# pic32.net
KiCad netlist of a schematic drawn in EAGLE
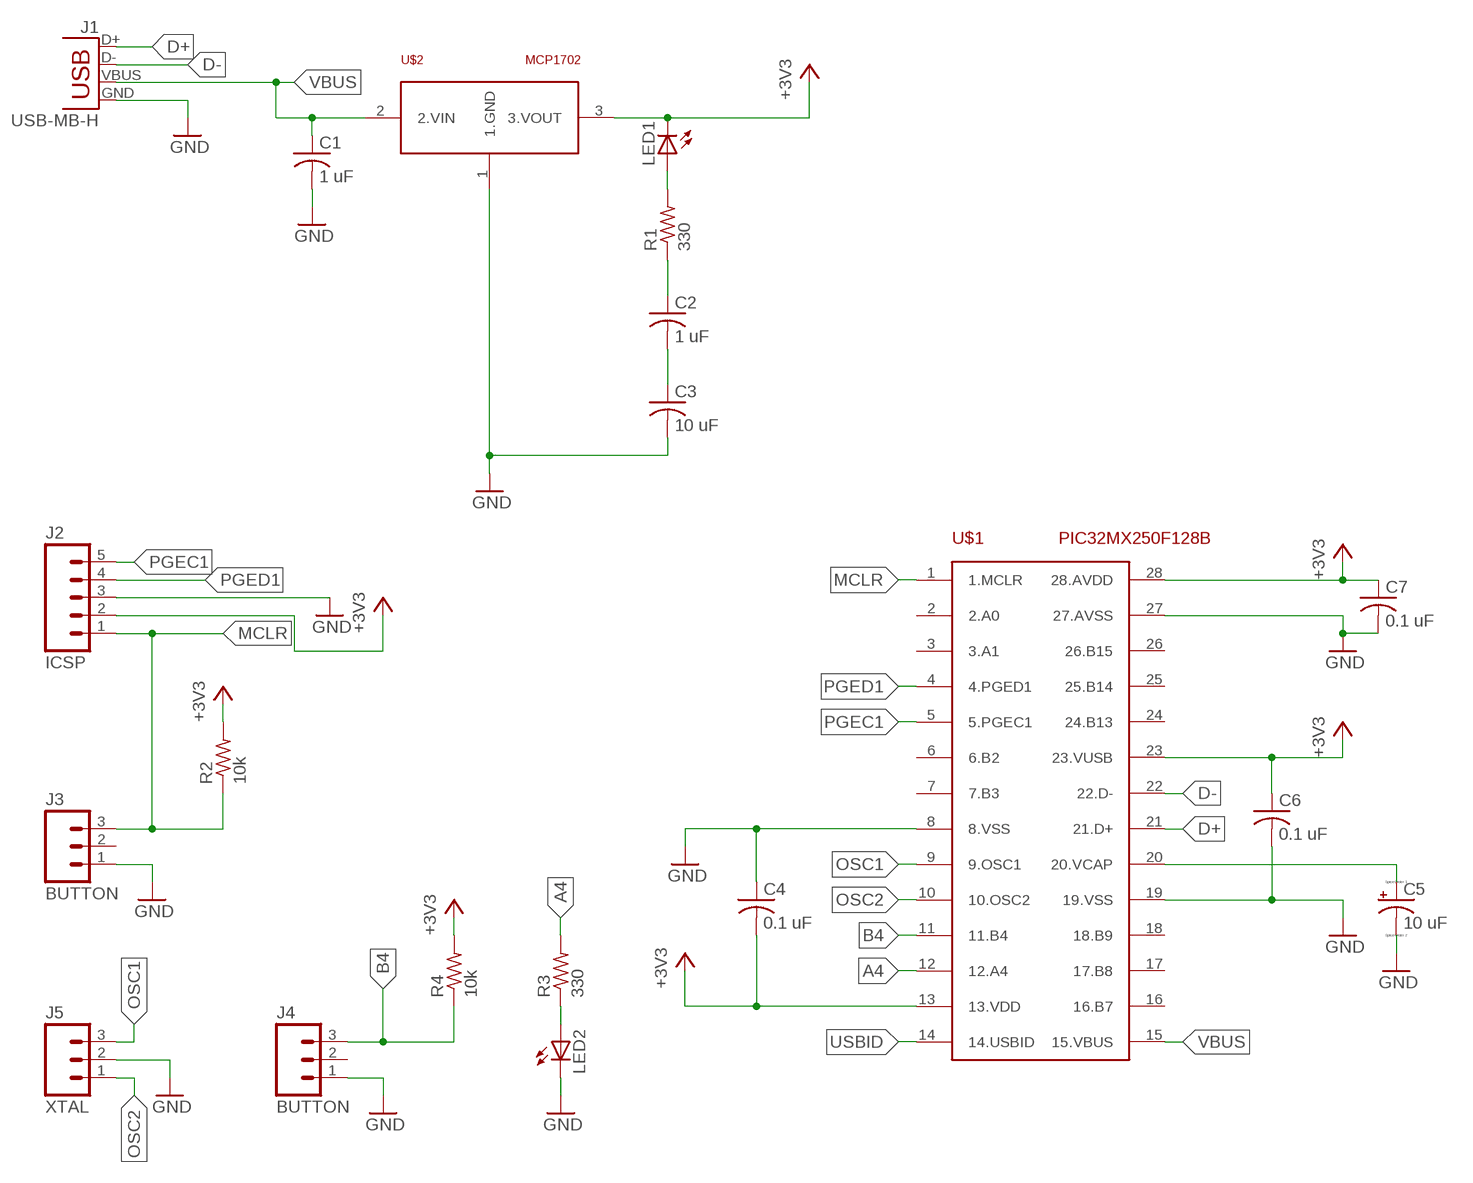
[diagram p0: schematic, sheet 1]

(export (version "E")
  (design (tool "Eeschema 10.0.6"))
  (components
    (comp (ref "C1")
      (value "1 uF")
      (footprint "eagle-import:C025-024X044")
      (libsource (lib "eagle-import") (part "C-US025-024X044"))
    )
    (comp (ref "C2")
      (value "1 uF")
      (footprint "eagle-import:C025-024X044")
      (libsource (lib "eagle-import") (part "C-US025-024X044"))
    )
    (comp (ref "C3")
      (value "10 uF")
      (footprint "eagle-import:C025-024X044")
      (libsource (lib "eagle-import") (part "C-US025-024X044"))
    )
    (comp (ref "C4")
      (value "0.1 uF")
      (footprint "eagle-import:C025-024X044")
      (libsource (lib "eagle-import") (part "C-US025-024X044"))
    )
    (comp (ref "C5")
      (value "10 uF")
      (footprint "eagle-import:E1,8-4")
      (libsource (lib "eagle-import") (part "CPOL-USE1.8-4"))
    )
    (comp (ref "C6")
      (value "0.1 uF")
      (footprint "eagle-import:C025-024X044")
      (libsource (lib "eagle-import") (part "C-US025-024X044"))
    )
    (comp (ref "C7")
      (value "0.1 uF")
      (footprint "eagle-import:C025-024X044")
      (libsource (lib "eagle-import") (part "C-US025-024X044"))
    )
    (comp (ref "J1")
      (value "USB-MB-H")
      (footprint "eagle-import:USB-MB-H")
      (libsource (lib "eagle-import") (part "USB-MB-H"))
    )
    (comp (ref "J2")
      (value "ICSP")
      (footprint "eagle-import:1X05")
      (libsource (lib "eagle-import") (part "M05PTH"))
    )
    (comp (ref "J3")
      (value "BUTTON")
      (footprint "eagle-import:1X03")
      (libsource (lib "eagle-import") (part "M03PTH"))
    )
    (comp (ref "J4")
      (value "BUTTON")
      (footprint "eagle-import:1X03")
      (libsource (lib "eagle-import") (part "M03PTH"))
    )
    (comp (ref "J5")
      (value "XTAL")
      (footprint "eagle-import:1X03")
      (libsource (lib "eagle-import") (part "M03PTH"))
    )
    (comp (ref "LED1")
      (value "LED3MM")
      (footprint "eagle-import:LED3MM")
      (libsource (lib "eagle-import") (part "LED3MM"))
    )
    (comp (ref "LED2")
      (value "LED3MM")
      (footprint "eagle-import:LED3MM")
      (libsource (lib "eagle-import") (part "LED3MM"))
    )
    (comp (ref "R1")
      (value "330")
      (footprint "eagle-import:0207_10")
      (libsource (lib "eagle-import") (part "R-US_0207/10"))
    )
    (comp (ref "R2")
      (value "10k")
      (footprint "eagle-import:0207_10")
      (libsource (lib "eagle-import") (part "R-US_0207/10"))
    )
    (comp (ref "R3")
      (value "330")
      (footprint "eagle-import:0207_10")
      (libsource (lib "eagle-import") (part "R-US_0207/10"))
    )
    (comp (ref "R4")
      (value "10k")
      (footprint "eagle-import:0207_10")
      (libsource (lib "eagle-import") (part "R-US_0207/10"))
    )
    (comp (ref "U$1")
      (value "PIC32MX250F128B")
      (footprint "eagle-import:DIL28-3")
      (libsource (lib "eagle-import") (part "PIC32MX250F128B"))
    )
    (comp (ref "U$2")
      (value "MCP1702")
      (footprint "eagle-import:TO92")
      (libsource (lib "eagle-import") (part "MCP1702"))
    )
  )
  (nets
    (net (code "1") (name "+3V3") (class "Default")
      (node (ref "C4") (pin "2") (pinfunction "2_2") (pintype "passive"))
      (node (ref "C6") (pin "1") (pinfunction "1_1") (pintype "passive"))
      (node (ref "C7") (pin "1") (pinfunction "1_1") (pintype "passive"))
      (node (ref "J2") (pin "2") (pinfunction "2_2") (pintype "passive"))
      (node (ref "LED1") (pin "K") (pinfunction "C_K") (pintype "passive"))
      (node (ref "R2") (pin "2") (pinfunction "2_2") (pintype "passive"))
      (node (ref "R4") (pin "2") (pinfunction "2_2") (pintype "passive"))
      (node (ref "U$1") (pin "13") (pinfunction "13.VDD_13") (pintype "bidirectional"))
      (node (ref "U$1") (pin "23") (pinfunction "23.VUSB_23") (pintype "bidirectional"))
      (node (ref "U$1") (pin "28") (pinfunction "28.AVDD_28") (pintype "bidirectional"))
      (node (ref "U$2") (pin "3") (pinfunction "3.VOUT_3") (pintype "bidirectional"))
    )
    (net (code "2") (name "A4") (class "Default")
      (node (ref "R3") (pin "2") (pinfunction "2_2") (pintype "passive"))
      (node (ref "U$1") (pin "12") (pinfunction "12.A4_12") (pintype "bidirectional"))
    )
    (net (code "3") (name "B4") (class "Default")
      (node (ref "J4") (pin "3") (pinfunction "3_3") (pintype "passive"))
      (node (ref "R4") (pin "1") (pinfunction "1_1") (pintype "passive"))
      (node (ref "U$1") (pin "11") (pinfunction "11.B4_11") (pintype "bidirectional"))
    )
    (net (code "4") (name "D+") (class "Default")
      (node (ref "J1") (pin "D+") (pinfunction "D+_D+") (pintype "bidirectional"))
      (node (ref "U$1") (pin "21") (pinfunction "21.D+_21") (pintype "bidirectional"))
    )
    (net (code "5") (name "D-") (class "Default")
      (node (ref "J1") (pin "D-") (pinfunction "D-_D-") (pintype "bidirectional"))
      (node (ref "U$1") (pin "22") (pinfunction "22.D-_22") (pintype "bidirectional"))
    )
    (net (code "6") (name "GND") (class "Default")
      (node (ref "C1") (pin "2") (pinfunction "2_2") (pintype "passive"))
      (node (ref "C3") (pin "2") (pinfunction "2_2") (pintype "passive"))
      (node (ref "C4") (pin "1") (pinfunction "1_1") (pintype "passive"))
      (node (ref "C5") (pin "-") (pinfunction "-_-") (pintype "passive"))
      (node (ref "C6") (pin "2") (pinfunction "2_2") (pintype "passive"))
      (node (ref "C7") (pin "2") (pinfunction "2_2") (pintype "passive"))
      (node (ref "J1") (pin "GND") (pinfunction "GND_GND") (pintype "bidirectional"))
      (node (ref "J2") (pin "3") (pinfunction "3_3") (pintype "passive"))
      (node (ref "J3") (pin "1") (pinfunction "1_1") (pintype "passive"))
      (node (ref "J4") (pin "1") (pinfunction "1_1") (pintype "passive"))
      (node (ref "J5") (pin "2") (pinfunction "2_2") (pintype "passive"))
      (node (ref "LED2") (pin "K") (pinfunction "C_K") (pintype "passive"))
      (node (ref "U$1") (pin "19") (pinfunction "19.VSS_19") (pintype "bidirectional"))
      (node (ref "U$1") (pin "27") (pinfunction "27.AVSS_27") (pintype "bidirectional"))
      (node (ref "U$1") (pin "8") (pinfunction "8.VSS_8") (pintype "bidirectional"))
      (node (ref "U$2") (pin "1") (pinfunction "1.GND_1") (pintype "bidirectional"))
    )
    (net (code "7") (name "MCLR") (class "Default")
      (node (ref "J2") (pin "1") (pinfunction "1_1") (pintype "passive"))
      (node (ref "J3") (pin "3") (pinfunction "3_3") (pintype "passive"))
      (node (ref "R2") (pin "1") (pinfunction "1_1") (pintype "passive"))
      (node (ref "U$1") (pin "1") (pinfunction "1.MCLR_1") (pintype "bidirectional"))
    )
    (net (code "8") (name "Net-(C2-Pad1)") (class "Default")
      (node (ref "C2") (pin "1") (pinfunction "1_1") (pintype "passive"))
      (node (ref "R1") (pin "1") (pinfunction "1_1") (pintype "passive"))
    )
    (net (code "9") (name "Net-(C2-Pad2)") (class "Default")
      (node (ref "C2") (pin "2") (pinfunction "2_2") (pintype "passive"))
      (node (ref "C3") (pin "1") (pinfunction "1_1") (pintype "passive"))
    )
    (net (code "10") (name "Net-(LED1-PadA)") (class "Default")
      (node (ref "LED1") (pin "A") (pinfunction "A_A") (pintype "passive"))
      (node (ref "R1") (pin "2") (pinfunction "2_2") (pintype "passive"))
    )
    (net (code "11") (name "Net-(LED2-PadA)") (class "Default")
      (node (ref "LED2") (pin "A") (pinfunction "A_A") (pintype "passive"))
      (node (ref "R3") (pin "1") (pinfunction "1_1") (pintype "passive"))
    )
    (net (code "12") (name "Net-(U$1-20.VCAP)") (class "Default")
      (node (ref "C5") (pin "+") (pinfunction "+_+") (pintype "passive"))
      (node (ref "U$1") (pin "20") (pinfunction "20.VCAP_20") (pintype "bidirectional"))
    )
    (net (code "13") (name "OSC1") (class "Default")
      (node (ref "J5") (pin "3") (pinfunction "3_3") (pintype "passive"))
      (node (ref "U$1") (pin "9") (pinfunction "9.OSC1_9") (pintype "bidirectional"))
    )
    (net (code "14") (name "OSC2") (class "Default")
      (node (ref "J5") (pin "1") (pinfunction "1_1") (pintype "passive"))
      (node (ref "U$1") (pin "10") (pinfunction "10.OSC2_10") (pintype "bidirectional"))
    )
    (net (code "15") (name "PGEC1") (class "Default")
      (node (ref "J2") (pin "5") (pinfunction "5_5") (pintype "passive"))
      (node (ref "U$1") (pin "5") (pinfunction "5.PGEC1_5") (pintype "bidirectional"))
    )
    (net (code "16") (name "PGED1") (class "Default")
      (node (ref "J2") (pin "4") (pinfunction "4_4") (pintype "passive"))
      (node (ref "U$1") (pin "4") (pinfunction "4.PGED1_4") (pintype "bidirectional"))
    )
    (net (code "17") (name "USBID") (class "Default")
      (node (ref "U$1") (pin "14") (pinfunction "14.USBID_14") (pintype "bidirectional"))
    )
    (net (code "18") (name "VBUS") (class "Default")
      (node (ref "C1") (pin "1") (pinfunction "1_1") (pintype "passive"))
      (node (ref "J1") (pin "VBUS") (pinfunction "VBUS_VBUS") (pintype "bidirectional"))
      (node (ref "U$1") (pin "15") (pinfunction "15.VBUS_15") (pintype "bidirectional"))
      (node (ref "U$2") (pin "2") (pinfunction "2.VIN_2") (pintype "bidirectional"))
    )
    (net (code "19") (name "unconnected-(J3-Pad2)") (class "Default")
      (node (ref "J3") (pin "2") (pinfunction "2_2") (pintype "passive"))
    )
    (net (code "20") (name "unconnected-(J4-Pad2)") (class "Default")
      (node (ref "J4") (pin "2") (pinfunction "2_2") (pintype "passive"))
    )
    (net (code "21") (name "unconnected-(U$1-2.A0-Pad2)") (class "Default")
      (node (ref "U$1") (pin "2") (pinfunction "2.A0_2") (pintype "bidirectional"))
    )
    (net (code "22") (name "unconnected-(U$1-3.A1-Pad3)") (class "Default")
      (node (ref "U$1") (pin "3") (pinfunction "3.A1_3") (pintype "bidirectional"))
    )
    (net (code "23") (name "unconnected-(U$1-6.B2-Pad6)") (class "Default")
      (node (ref "U$1") (pin "6") (pinfunction "6.B2_6") (pintype "bidirectional"))
    )
    (net (code "24") (name "unconnected-(U$1-7.B3-Pad7)") (class "Default")
      (node (ref "U$1") (pin "7") (pinfunction "7.B3_7") (pintype "bidirectional"))
    )
    (net (code "25") (name "unconnected-(U$1-16.B7-Pad16)") (class "Default")
      (node (ref "U$1") (pin "16") (pinfunction "16.B7_16") (pintype "bidirectional"))
    )
    (net (code "26") (name "unconnected-(U$1-17.B8-Pad17)") (class "Default")
      (node (ref "U$1") (pin "17") (pinfunction "17.B8_17") (pintype "bidirectional"))
    )
    (net (code "27") (name "unconnected-(U$1-18.B9-Pad18)") (class "Default")
      (node (ref "U$1") (pin "18") (pinfunction "18.B9_18") (pintype "bidirectional"))
    )
    (net (code "28") (name "unconnected-(U$1-24.B13-Pad24)") (class "Default")
      (node (ref "U$1") (pin "24") (pinfunction "24.B13_24") (pintype "bidirectional"))
    )
    (net (code "29") (name "unconnected-(U$1-25.B14-Pad25)") (class "Default")
      (node (ref "U$1") (pin "25") (pinfunction "25.B14_25") (pintype "bidirectional"))
    )
    (net (code "30") (name "unconnected-(U$1-26.B15-Pad26)") (class "Default")
      (node (ref "U$1") (pin "26") (pinfunction "26.B15_26") (pintype "bidirectional"))
    )
  )
)
